# Blinky_Stick_Schematic.net
KiCad netlist of a schematic drawn in Altium Designer
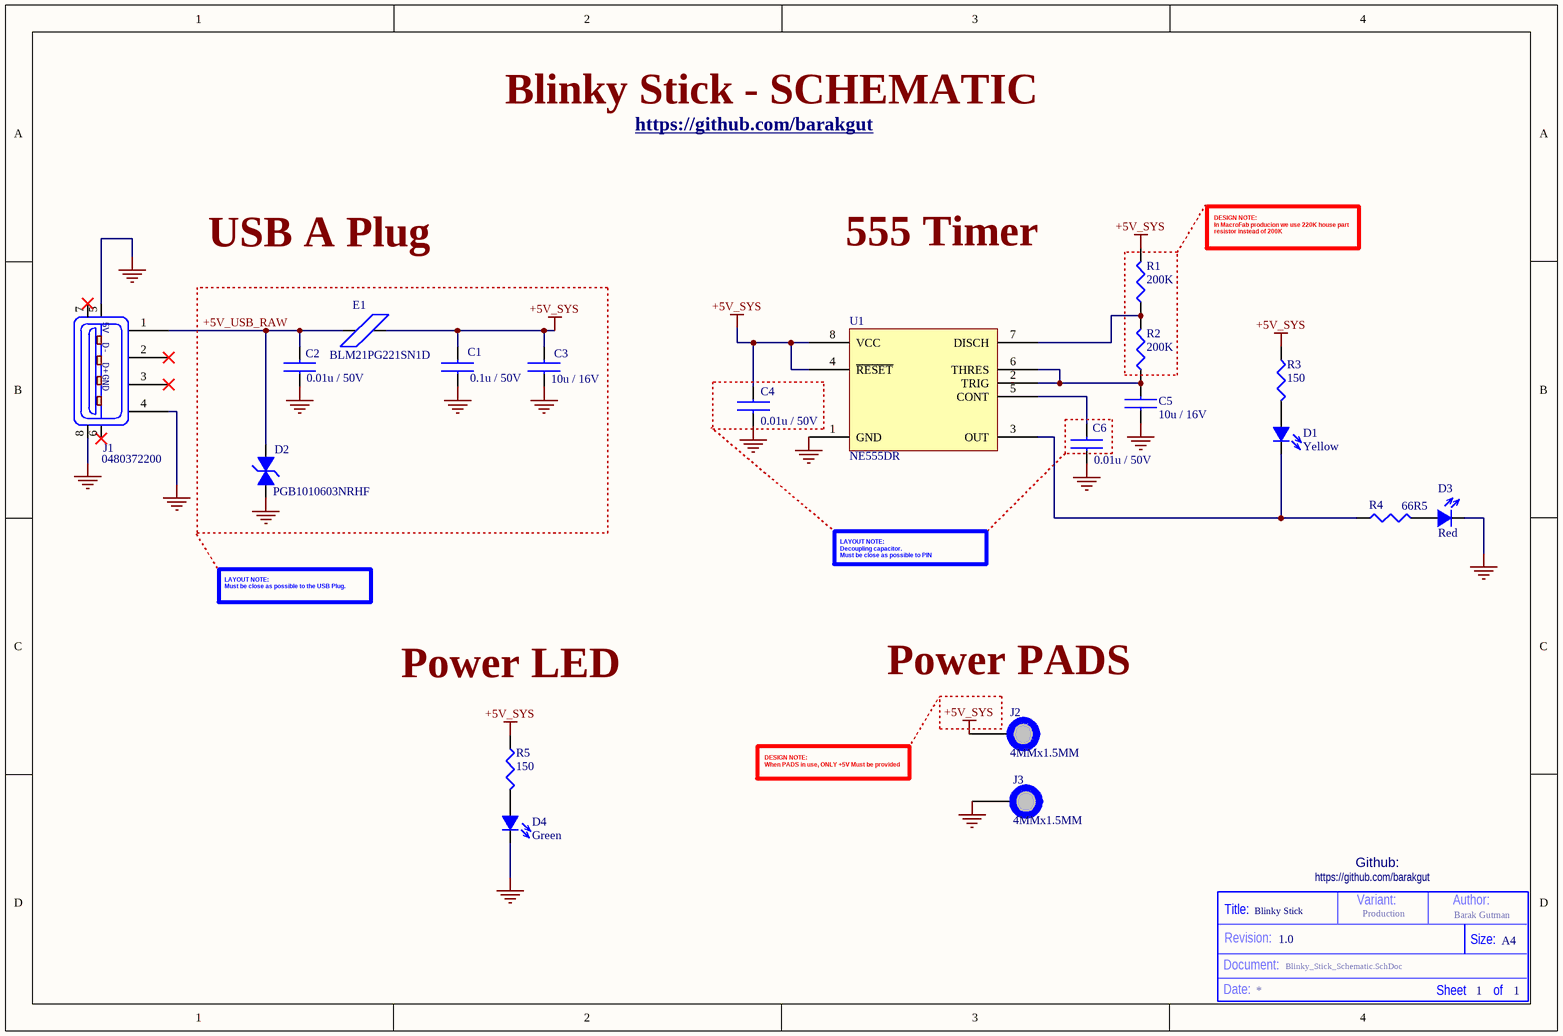
[diagram p0: Blinky_Stick_Schematic.SchDoc]

(export (version "E")
  (design (tool "Eeschema 10.0.6"))
  (components
    (comp (ref "C1")
      (value "0.1u / 50V")
      (footprint "C0805")
      (description "CAP CER 0.1UF 50V X7R 0805")
      (fields
        (field (name "MANUFACTURER") "TDK Corporation")
        (field (name "MANUFACTURER PART NUMBER") "C2012X7R1H104K085AA")
      )
      (libsource (lib "Blinky_Stick") (part "C2012X7R1H104K085AA"))
    )
    (comp (ref "C2")
      (value "0.01u / 50V")
      (footprint "C0805")
      (description "CAP CER 10000PF 50V C0G 0805")
      (fields
        (field (name "MANUFACTURER") "TDK Corporation")
        (field (name "MANUFACTURER PART NUMBER") "C2012C0G1H103K060AA")
      )
      (libsource (lib "Blinky_Stick") (part "C2012C0G1H103K060AA"))
    )
    (comp (ref "C3")
      (value "10u / 16V")
      (footprint "C0805")
      (description "CAP CER 10UF 16V X5R 0805")
      (fields
        (field (name "MANUFACTURER") "TDK Corporation")
        (field (name "MANUFACTURER PART NUMBER") "C2012X5R1C106K085AC")
      )
      (libsource (lib "Blinky_Stick") (part "C2012X5R1C106K085AC"))
    )
    (comp (ref "C4")
      (value "0.01u / 50V")
      (footprint "C0805")
      (description "CAP CER 10000PF 50V C0G 0805")
      (fields
        (field (name "MANUFACTURER") "TDK Corporation")
        (field (name "MANUFACTURER PART NUMBER") "C2012C0G1H103K060AA")
      )
      (libsource (lib "Blinky_Stick") (part "C2012C0G1H103K060AA"))
    )
    (comp (ref "C5")
      (value "10u / 16V")
      (footprint "C0805")
      (description "CAP CER 10UF 16V X5R 0805")
      (fields
        (field (name "MANUFACTURER") "TDK Corporation")
        (field (name "MANUFACTURER PART NUMBER") "C2012X5R1C106K085AC")
      )
      (libsource (lib "Blinky_Stick") (part "C2012X5R1C106K085AC"))
    )
    (comp (ref "C6")
      (value "0.01u / 50V")
      (footprint "C0805")
      (description "CAP CER 10000PF 50V C0G 0805")
      (fields
        (field (name "MANUFACTURER") "TDK Corporation")
        (field (name "MANUFACTURER PART NUMBER") "C2012C0G1H103K060AA")
      )
      (libsource (lib "Blinky_Stick") (part "C2012C0G1H103K060AA"))
    )
    (comp (ref "D1")
      (value "Yellow")
      (footprint "LED0805")
      (description "LED YELLOW CLEAR 0805 SMD")
      (fields
        (field (name "MANUFACTURER") "Lite-On Inc.")
        (field (name "MANUFACTURER PART NUMBER") "LTST-C171KSKT")
      )
      (libsource (lib "Blinky_Stick") (part "LTST-C171KSKT"))
    )
    (comp (ref "D2")
      (value "PGB1010603NRHF")
      (footprint "DIODE_0603")
      (description "TVS DIODE 24VWM 150VC 0603")
      (fields (field (name "MANUFACTURER") "Littelfuse Inc."))
      (libsource (lib "Blinky_Stick") (part "PGB1010603NRHF"))
    )
    (comp (ref "D3")
      (value "Red")
      (footprint "LED0805")
      (description "LED RED CLEAR 0805 SMD")
      (fields
        (field (name "MANUFACTURER") "Lite-On Inc.")
        (field (name "MANUFACTURER PART NUMBER") "LTST-C171KRKT")
      )
      (libsource (lib "Blinky_Stick") (part "LTST-C171KRKT"))
    )
    (comp (ref "D4")
      (value "Green")
      (footprint "LED0805")
      (description "LED GREEN CLEAR 0805 SMD")
      (fields
        (field (name "MANUFACTURER") "Lite-On Inc.")
        (field (name "MANUFACTURER PART NUMBER") "LTST-C171GKT")
      )
      (libsource (lib "Blinky_Stick") (part "LTST-C171GKT"))
    )
    (comp (ref "E1")
      (value "BLM21PG221SN1D")
      (footprint "C0805")
      (description "FERRITE BEAD 220 OHM 0805 1LN")
      (fields (field (name "MANUFACTURER") "Murata Electronics North America"))
      (libsource (lib "Blinky_Stick") (part "BLM21PG221SN1D"))
    )
    (comp (ref "J1")
      (value "0480372200")
      (footprint "0480372200")
      (description "CONN PLUG USB A 4POS SMD R/A")
      (fields (field (name "MANUFACTURER") "Molex, LLC"))
      (libsource (lib "Blinky_Stick") (part "0480372200"))
    )
    (comp (ref "J2")
      (value "4MMx1.5MM")
      (footprint "PAD_WITH_HOLE_4MMx1.5MM")
      (description "Pad with hole 4mm x 1.5mm")
      (libsource (lib "Blinky_Stick") (part "PAD_WITH_HOLE_4MMx1.5MM"))
    )
    (comp (ref "J3")
      (value "4MMx1.5MM")
      (footprint "PAD_WITH_HOLE_4MMx1.5MM")
      (description "Pad with hole 4mm x 1.5mm")
      (libsource (lib "Blinky_Stick") (part "PAD_WITH_HOLE_4MMx1.5MM"))
    )
    (comp (ref "R1")
      (value "200K")
      (footprint "R0805")
      (description "RES SMD 200K OHM 1% 1/8W 0805")
      (fields
        (field (name "MANUFACTURER") "Yageo")
        (field (name "MANUFACTURER PART NUMBER") "RC0805FR-07200KL")
      )
      (libsource (lib "Blinky_Stick") (part "RC0805FR-07200KL"))
    )
    (comp (ref "R2")
      (value "200K")
      (footprint "R0805")
      (description "RES SMD 200K OHM 1% 1/8W 0805")
      (fields
        (field (name "MANUFACTURER") "Yageo")
        (field (name "MANUFACTURER PART NUMBER") "RC0805FR-07200KL")
      )
      (libsource (lib "Blinky_Stick") (part "RC0805FR-07200KL"))
    )
    (comp (ref "R3")
      (value "150")
      (footprint "R0805")
      (description "RES SMD 150 OHM 1% 1/8W 0805")
      (fields
        (field (name "MANUFACTURER") "Yageo")
        (field (name "MANUFACTURER PART NUMBER") "RC0805FR-07150RL")
      )
      (libsource (lib "Blinky_Stick") (part "RC0805FR-07150RL"))
    )
    (comp (ref "R4")
      (value "66R5")
      (footprint "R0805")
      (description "RES SMD 66.5 OHM 1% 1/8W 0805")
      (fields
        (field (name "MANUFACTURER") "Yageo")
        (field (name "MANUFACTURER PART NUMBER") "RC0805FR-0766R5L")
      )
      (libsource (lib "Blinky_Stick") (part "RC0805FR-0766R5L"))
    )
    (comp (ref "R5")
      (value "150")
      (footprint "R0805")
      (description "RES SMD 150 OHM 1% 1/8W 0805")
      (fields
        (field (name "MANUFACTURER") "Yageo")
        (field (name "MANUFACTURER PART NUMBER") "RC0805FR-07150RL")
      )
      (libsource (lib "Blinky_Stick") (part "RC0805FR-07150RL"))
    )
    (comp (ref "U1")
      (value "NE555DR")
      (footprint "SOIC-8_D_R-PDSO-G8")
      (description "IC OSC SGL TIMER 100KHZ 8-SOIC")
      (fields (field (name "MANUFACTURER") "Texas Instruments"))
      (libsource (lib "Blinky_Stick") (part "NE555DR"))
    )
  )
  (nets
    (net (code "1") (name "+5V_SYS") (class "Default")
      (node (ref "C1") (pin "2") (pinfunction "2_2") (pintype "passive"))
      (node (ref "C3") (pin "2") (pinfunction "2_2") (pintype "passive"))
      (node (ref "C4") (pin "2") (pinfunction "2_2") (pintype "passive"))
      (node (ref "E1") (pin "2") (pinfunction "2_2") (pintype "passive"))
      (node (ref "J2") (pin "1") (pinfunction "1_1") (pintype "passive"))
      (node (ref "R1") (pin "2") (pinfunction "2_2") (pintype "passive"))
      (node (ref "R3") (pin "1") (pinfunction "1_1") (pintype "passive"))
      (node (ref "R5") (pin "1") (pinfunction "1_1") (pintype "passive"))
      (node (ref "U1") (pin "4") (pinfunction "~{RESET}_4") (pintype "passive"))
      (node (ref "U1") (pin "8") (pinfunction "VCC_8") (pintype "passive"))
    )
    (net (code "2") (name "/+5V_USB_RAW") (class "Default")
      (node (ref "C2") (pin "2") (pinfunction "2_2") (pintype "passive"))
      (node (ref "D2") (pin "2") (pinfunction "2_2") (pintype "passive"))
      (node (ref "E1") (pin "1") (pinfunction "1_1") (pintype "passive"))
      (node (ref "J1") (pin "1") (pinfunction "5V_1") (pintype "passive"))
    )
    (net (code "3") (name "GND") (class "Default")
      (node (ref "C1") (pin "1") (pinfunction "1_1") (pintype "passive"))
      (node (ref "C2") (pin "1") (pinfunction "1_1") (pintype "passive"))
      (node (ref "C3") (pin "1") (pinfunction "1_1") (pintype "passive"))
      (node (ref "C4") (pin "1") (pinfunction "1_1") (pintype "passive"))
      (node (ref "C5") (pin "1") (pinfunction "1_1") (pintype "passive"))
      (node (ref "C6") (pin "1") (pinfunction "1_1") (pintype "passive"))
      (node (ref "D2") (pin "1") (pinfunction "1_1") (pintype "passive"))
      (node (ref "D3") (pin "2") (pinfunction "Cathode_2") (pintype "passive"))
      (node (ref "D4") (pin "2") (pinfunction "Cathode_2") (pintype "passive"))
      (node (ref "J1") (pin "4") (pinfunction "GND_4") (pintype "passive"))
      (node (ref "J1") (pin "5") (pinfunction "GND_5") (pintype "passive"))
      (node (ref "J1") (pin "8") (pinfunction "MH_8") (pintype "passive"))
      (node (ref "J3") (pin "1") (pinfunction "1_1") (pintype "passive"))
      (node (ref "U1") (pin "1") (pinfunction "GND_1") (pintype "passive"))
    )
    (net (code "4") (name "Net-(D1-Anode)") (class "Default")
      (node (ref "D1") (pin "1") (pinfunction "Anode_1") (pintype "passive"))
      (node (ref "R3") (pin "2") (pinfunction "2_2") (pintype "passive"))
    )
    (net (code "5") (name "Net-(D1-Cathode)") (class "Default")
      (node (ref "D1") (pin "2") (pinfunction "Cathode_2") (pintype "passive"))
      (node (ref "R4") (pin "1") (pinfunction "1_1") (pintype "passive"))
      (node (ref "U1") (pin "3") (pinfunction "OUT_3") (pintype "passive"))
    )
    (net (code "6") (name "Net-(D3-Anode)") (class "Default")
      (node (ref "D3") (pin "1") (pinfunction "Anode_1") (pintype "passive"))
      (node (ref "R4") (pin "2") (pinfunction "2_2") (pintype "passive"))
    )
    (net (code "7") (name "Net-(D4-Anode)") (class "Default")
      (node (ref "D4") (pin "1") (pinfunction "Anode_1") (pintype "passive"))
      (node (ref "R5") (pin "2") (pinfunction "2_2") (pintype "passive"))
    )
    (net (code "8") (name "Net-(U1-CONT)") (class "Default")
      (node (ref "C6") (pin "2") (pinfunction "2_2") (pintype "passive"))
      (node (ref "U1") (pin "5") (pinfunction "CONT_5") (pintype "passive"))
    )
    (net (code "9") (name "Net-(U1-DISCH)") (class "Default")
      (node (ref "R1") (pin "1") (pinfunction "1_1") (pintype "passive"))
      (node (ref "R2") (pin "2") (pinfunction "2_2") (pintype "passive"))
      (node (ref "U1") (pin "7") (pinfunction "DISCH_7") (pintype "passive"))
    )
    (net (code "10") (name "Net-(U1-THRES)") (class "Default")
      (node (ref "C5") (pin "2") (pinfunction "2_2") (pintype "passive"))
      (node (ref "R2") (pin "1") (pinfunction "1_1") (pintype "passive"))
      (node (ref "U1") (pin "2") (pinfunction "TRIG_2") (pintype "passive"))
      (node (ref "U1") (pin "6") (pinfunction "THRES_6") (pintype "passive"))
    )
    (net (code "11") (name "unconnected-(J1-DM-Pad2)") (class "Default")
      (node (ref "J1") (pin "2") (pinfunction "DM_2") (pintype "passive+no_connect"))
    )
    (net (code "12") (name "unconnected-(J1-DP-Pad3)") (class "Default")
      (node (ref "J1") (pin "3") (pinfunction "DP_3") (pintype "passive+no_connect"))
    )
    (net (code "13") (name "unconnected-(J1-GND-Pad6)") (class "Default")
      (node (ref "J1") (pin "6") (pinfunction "GND_6") (pintype "passive+no_connect"))
    )
    (net (code "14") (name "unconnected-(J1-MH-Pad7)") (class "Default")
      (node (ref "J1") (pin "7") (pinfunction "MH_7") (pintype "passive+no_connect"))
    )
  )
)
